# Sensor.net
KiCad netlist of a schematic drawn in Altium Designer
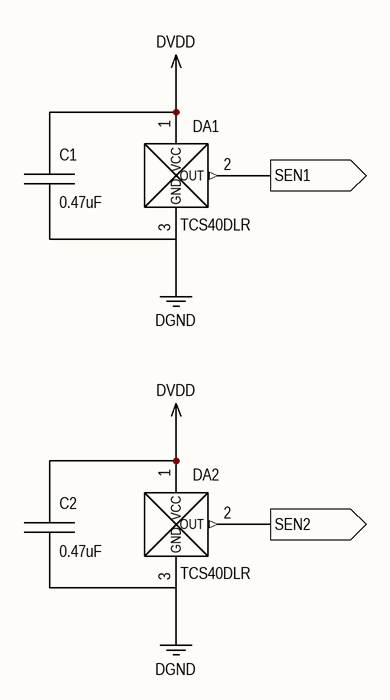
[diagram p0: Sensor.SchDoc]

(export (version "E")
  (design (tool "Eeschema 10.0.6"))
  (components
    (comp (ref "C1")
      (value "0.47uF")
      (footprint "CAPC1608L")
      (description "Capacitor Ceramic 0.47uF 10V")
      (fields (field (name "TOLERANCE") "±10%") (field (name "MANUFACTURER") "Yageo"))
      (libsource (lib "Capacitors") (part "CC0603KRX7R6BB474"))
    )
    (comp (ref "C2")
      (value "0.47uF")
      (footprint "CAPC1608L")
      (description "Capacitor Ceramic 0.47uF 10V")
      (fields (field (name "TOLERANCE") "±10%") (field (name "MANUFACTURER") "Yageo"))
      (libsource (lib "Capacitors") (part "CC0603KRX7R6BB474"))
    )
    (comp (ref "DA1")
      (value "TCS40DLR")
      (footprint "SOT-23F")
      (description "Magnetic Sensor Digital Output")
      (fields (field (name "MANUFACTURER") "TOSHIBA"))
      (libsource (lib "Discrete components") (part "TCS40DLR"))
    )
    (comp (ref "DA2")
      (value "TCS40DLR")
      (footprint "SOT-23F")
      (description "Magnetic Sensor Digital Output")
      (fields (field (name "MANUFACTURER") "TOSHIBA"))
      (libsource (lib "Discrete components") (part "TCS40DLR"))
    )
  )
  (nets
    (net (code "1") (name "/SEN1") (class "Default")
      (node (ref "DA1") (pin "2") (pinfunction "OUT_2") (pintype "output"))
    )
    (net (code "2") (name "/SEN2") (class "Default")
      (node (ref "DA2") (pin "2") (pinfunction "OUT_2") (pintype "output"))
    )
    (net (code "3") (name "DGND") (class "Default")
      (node (ref "C1") (pin "2") (pinfunction "2_2") (pintype "passive"))
      (node (ref "C2") (pin "2") (pinfunction "2_2") (pintype "passive"))
      (node (ref "DA1") (pin "3") (pinfunction "GND_3") (pintype "passive"))
      (node (ref "DA2") (pin "3") (pinfunction "GND_3") (pintype "passive"))
    )
    (net (code "4") (name "DVDD") (class "Default")
      (node (ref "C1") (pin "1") (pinfunction "1_1") (pintype "passive"))
      (node (ref "C2") (pin "1") (pinfunction "1_1") (pintype "passive"))
      (node (ref "DA1") (pin "1") (pinfunction "VCC_1") (pintype "power_in"))
      (node (ref "DA2") (pin "1") (pinfunction "VCC_1") (pintype "power_in"))
    )
  )
)
